# MCU042A_Antenna_RF.net
KiCad netlist of a schematic drawn in Altium Designer
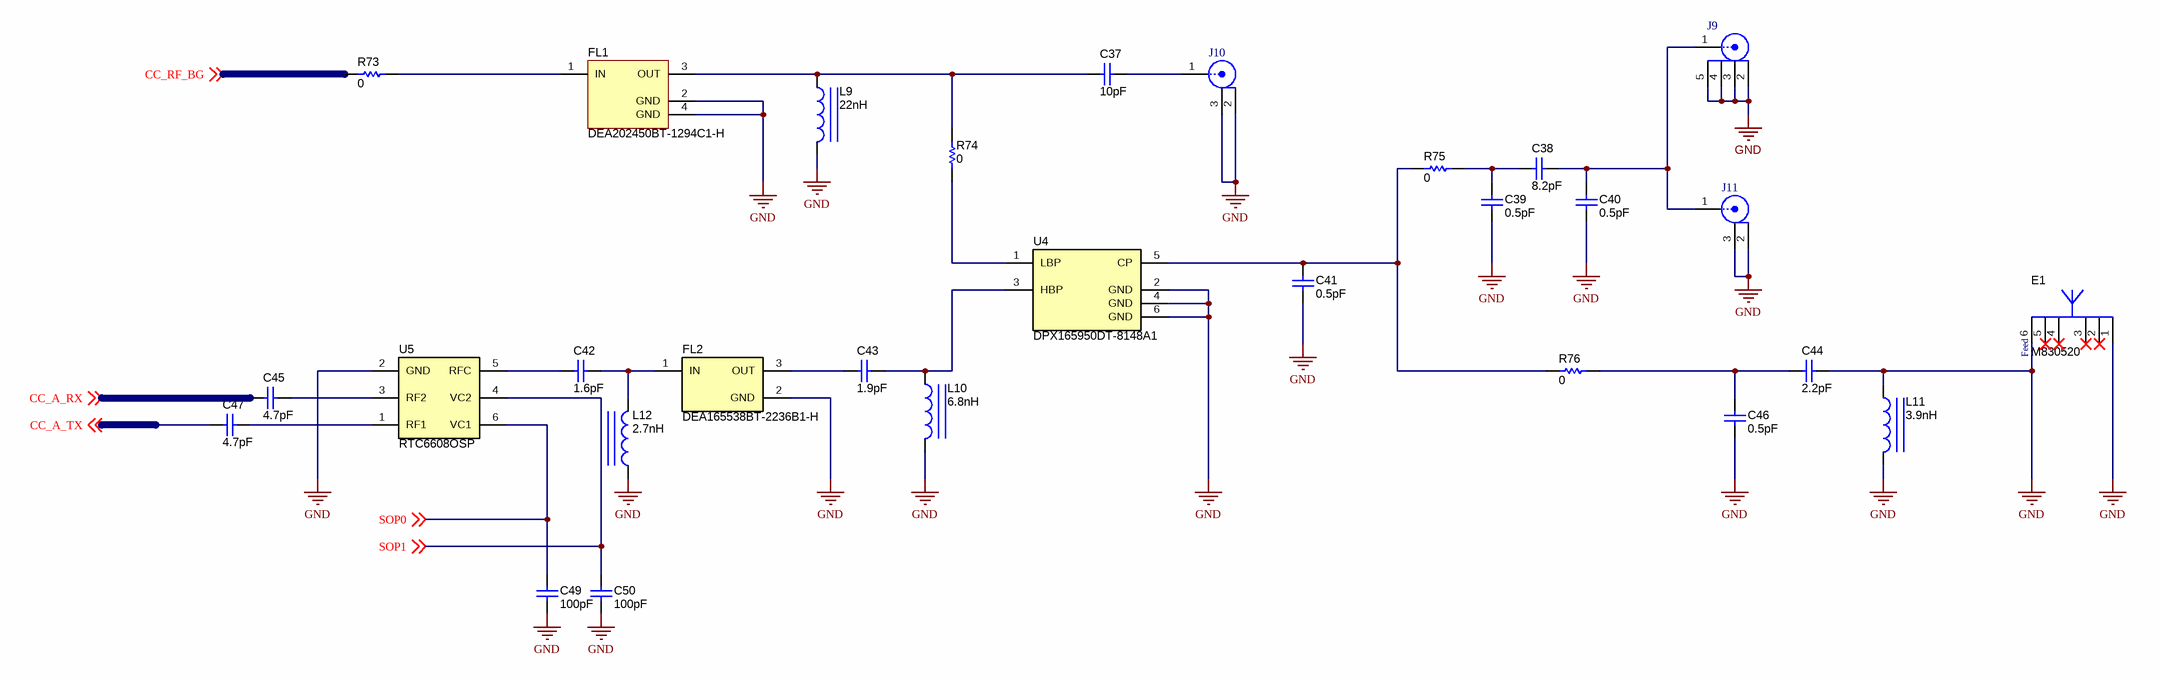
[diagram p0: MCU042A_Antenna_RF .SchDoc]

(export (version "E")
  (design (tool "Eeschema 10.0.6"))
  (components
    (comp (ref "C37")
      (value "CMP-0006408-2")
      (footprint "0402S")
      (description "CAP, CERM, 10 pF, 50 V, +/- 5%, C0G/NP0, 0402")
      (fields
        (field (name "PARTNUMBER") "GRM1555C1H100JA01D")
        (field (name "VALUEDISPLAYED") "10pF")
        (field (name "MANUFACTURER") "MuRata")
        (field (name "PUBLISHER") "Texas Instruments")
      )
      (libsource (lib "Altium Vault - TI") (part "CMP-0006408-2"))
    )
    (comp (ref "C38")
      (value "0402N8R2C500CT")
      (footprint "0402S")
      (description "CAP, CERM, 8.2 pF, 50 V,+/- 3%, C0G/NP0, 0402")
      (fields
        (field (name "PARTNUMBER") "GJM1555C1H8R2BB01D")
        (field (name "VALUEDISPLAYED") "8.2pF")
        (field (name "MANUFACTURER") "MuRata")
      )
      (libsource (lib "Altium Vault - TI") (part "Capacitor"))
    )
    (comp (ref "C39")
      (value "GJM1555C1HR50BB01J")
      (footprint "0402S")
      (description "CAP, CERM, 0.5 pF, 50 V,+/- 20%, C0G/NP0, 0402")
      (fields (field (name "VALUEDISPLAYED") "0.5pF") (field (name "MANUFACTURER") "MuRata"))
      (libsource (lib "Altium Vault - TI") (part "Capacitor"))
    )
    (comp (ref "C40")
      (value "GJM1555C1HR50BB01J")
      (footprint "0402S")
      (description "CAP, CERM, 0.5 pF, 50 V,+/- 20%, C0G/NP0, 0402")
      (fields (field (name "VALUEDISPLAYED") "0.5pF") (field (name "MANUFACTURER") "MuRata"))
      (libsource (lib "Altium Vault - TI") (part "Capacitor"))
    )
    (comp (ref "C41")
      (value "GJM1555C1HR50BB01J")
      (footprint "0402S")
      (description "CAP, CERM, 0.5 pF, 50 V,+/- 20%, C0G/NP0, 0402")
      (fields (field (name "VALUEDISPLAYED") "0.5pF") (field (name "MANUFACTURER") "MuRata"))
      (libsource (lib "Altium Vault - TI") (part "Capacitor"))
    )
    (comp (ref "C42")
      (value "GRM0335C1H1R6BA01D")
      (footprint "0201_033")
      (description "CAP, CERM, 1.6 pF, 50 V,+/- 7%, C0G/NP0, 0201")
      (fields (field (name "VALUEDISPLAYED") "1.6pF") (field (name "MANUFACTURER") "MuRata"))
      (libsource (lib "Altium Vault - TI") (part "Capacitor"))
    )
    (comp (ref "C43")
      (value "GJM1555C1H1R9WB01D")
      (footprint "0402S")
      (description "CAP, CERM, 1.9 pF, 50 V,+/- 2.6%, C0G/NP0, 0402")
      (fields
        (field (name "VALUEDISPLAYED") "1.9pF")
        (field (name "MANUFACTURER") "MuRata")
        (field (name "ALTERNATE PARTNUMBER") "GRM1555C1H1R9WA01D")
      )
      (libsource (lib "Altium Vault - TI") (part "Capacitor"))
    )
    (comp (ref "C44")
      (value "GJM1555C1H2R2BB01D")
      (footprint "0402S")
      (description "CAP, CERM, 2.2 pF, 50 V,+/- 4.5%, C0G/NP0, 0402")
      (fields
        (field (name "VALUEDISPLAYED") "2.2pF")
        (field (name "MANUFACTURER") "MuRata")
        (field (name "ALTERNATE PARTNUMBER") "GRM1555C1H2R2BA01D")
      )
      (libsource (lib "Altium Vault - TI") (part "Capacitor"))
    )
    (comp (ref "C45")
      (value "GRM0335C1H4R7BA01D")
      (footprint "0201_033")
      (description "CAP, CERM, 4.7 pF, 50 V,+/- 3%, C0G/NP0, 0201")
      (fields (field (name "VALUEDISPLAYED") "4.7pF") (field (name "MANUFACTURER") "MuRata"))
      (libsource (lib "Altium Vault - TI") (part "Capacitor"))
    )
    (comp (ref "C46")
      (value "GJM1555C1HR50BB01J")
      (footprint "0402S")
      (description "CAP, CERM, 0.5 pF, 50 V, +/- 10%, C0G/NP0, 0402")
      (fields
        (field (name "VALUEDISPLAYED") "0.5pF")
        (field (name "MANUFACTURER") "MuRata")
        (field (name "ALTERNATE PARTNUMBER") "----")
        (field (name "PUBLISHER") "Texas Instruments")
      )
      (libsource (lib "altium-import") (part "root_1_GRM1555C1H1R0BA01D_"))
    )
    (comp (ref "C47")
      (value "GRM0335C1H4R7BA01D")
      (footprint "0201_033")
      (description "CAP, CERM, 4.7 pF, 50 V,+/- 3%, C0G/NP0, 0201")
      (fields (field (name "VALUEDISPLAYED") "4.7pF") (field (name "MANUFACTURER") "MuRata"))
      (libsource (lib "Altium Vault - TI") (part "Capacitor"))
    )
    (comp (ref "C49")
      (value "CC0201JRNPO8BN101")
      (footprint "0201")
      (description "CAP, CERM, 100 pF, 25 V,+/- 5%, C0G/NP0, 0201")
      (fields
        (field (name "VALUEDISPLAYED") "100pF")
        (field (name "MANUFACTURER") "Yageo")
        (field (name "ALTERNATE PARTNUMBER") "C0603C0G1E101J030BA")
      )
      (libsource (lib "Altium Vault - TI") (part "Capacitor"))
    )
    (comp (ref "C50")
      (value "CC0201JRNPO8BN101")
      (footprint "0201")
      (description "CAP, CERM, 100 pF, 25 V,+/- 5%, C0G/NP0, 0201")
      (fields
        (field (name "VALUEDISPLAYED") "100pF")
        (field (name "MANUFACTURER") "Yageo")
        (field (name "ALTERNATE PARTNUMBER") "C0603C0G1E101J030BA")
      )
      (libsource (lib "Altium Vault - TI") (part "Capacitor"))
    )
    (comp (ref "E1")
      (value "M830520")
      (footprint "Ethertronics_M830520")
      (description "WLAN ANTENNA 802.11, SMD")
      (fields
        (field (name "MANUFACTURER") "Ethertronics")
        (field (name "ALTERNATE PARTNUMBER") "----")
        (field (name "PUBLISHER") "Texas Instruments")
      )
      (libsource (lib "Altium Vault - TI") (part "CMP-0001857-1"))
    )
    (comp (ref "FL1")
      (value "CMP-0002039-2")
      (footprint "TDK_DEA202450BT-1294C1-H")
      (description "Multilayer Chip Band Pass Filter For 2.4GHz W-LAN/Bluetooth, SMD")
      (fields
        (field (name "PARTNUMBER") "DEA202450BT-1294C1-H")
        (field (name "MANUFACTURER") "TDK")
        (field (name "ALTERNATE PARTNUMBER") "----")
        (field (name "PUBLISHER") "Texas Instruments")
      )
      (libsource (lib "Altium Vault - TI") (part "CMP-0002039-2"))
    )
    (comp (ref "FL2")
      (value "CMP-0002038-2")
      (footprint "TDK_DEA165538BT-2236B1-H")
      (description "Multilayer Band Pass Filter For 5GHz W-LAN/LTE-U")
      (fields
        (field (name "PARTNUMBER") "DEA165538BT-2236B1-H")
        (field (name "MANUFACTURER") "TDK")
        (field (name "ALTERNATE PARTNUMBER") "----")
        (field (name "PUBLISHER") "Texas Instruments")
      )
      (libsource (lib "Altium Vault - TI") (part "CMP-0002038-2"))
    )
    (comp (ref "J9")
      (value "CMP-0055832-1")
      (footprint "Hustsan_SMA-10V21-TGG")
      (description "Connector, SMA, Vertical, Gold, SMT")
      (fields
        (field (name "PARTNUMBER") "SMA-10V21-TGG")
        (field (name "MANUFACTURER") "Hus-Tsan Group Co., Ltd.")
        (field (name "PUBLISHER") "Texas Instruments")
      )
      (libsource (lib "Altium Vault - TI") (part "CMP-0055832-1"))
    )
    (comp (ref "J10")
      (value "U.FL-R-SMT-1(01)")
      (footprint "CONN_UFL-R-SMT-1")
      (description "Receptacle, Ultra Miniature Coaxial, Male Pin, 50 ohm, SMT")
      (fields
        (field (name "MANUFACTURER") "Hirose Electric Co. Ltd.")
        (field (name "ALTERNATE PARTNUMBER") "----")
        (field (name "PUBLISHER") "Texas Instruments")
      )
      (libsource (lib "Altium Vault - TI") (part "CMP-0075320-1"))
    )
    (comp (ref "J11")
      (value "U.FL-R-SMT-1(01)")
      (footprint "CONN_UFL-R-SMT-1")
      (description "Receptacle, Ultra Miniature Coaxial, Male Pin, 50 ohm, SMT")
      (fields
        (field (name "MANUFACTURER") "Hirose Electric Co. Ltd.")
        (field (name "ALTERNATE PARTNUMBER") "----")
        (field (name "PUBLISHER") "Texas Instruments")
      )
      (libsource (lib "Altium Vault - TI") (part "CMP-0075320-1"))
    )
    (comp (ref "L9")
      (value "LQG15HZ22NH02D")
      (footprint "0402S")
      (description "Inductor, Multilayer, Air Core, 22 nH, 0.35 A, 0.42 ohm, AEC-Q200 Grade 1, SMD")
      (fields (field (name "MANUFACTURER") "MuRata") (field (name "VALUEDISPLAYED") "22nH"))
      (libsource (lib "Altium Vault - TI") (part "Inductor_Iron"))
    )
    (comp (ref "L10")
      (value "LQG15HZ6N8H02D")
      (footprint "0402S")
      (description "Inductor, Multilayer, Air Core, 6.8 nH, 0.6 A, 0.22 ohm, AEC-Q200 Grade 1, SMD")
      (fields (field (name "MANUFACTURER") "MuRata") (field (name "VALUEDISPLAYED") "6.8nH"))
      (libsource (lib "Altium Vault - TI") (part "Inductor_Iron"))
    )
    (comp (ref "L11")
      (value "CMP-0058633-1")
      (footprint "IND_LQG15H")
      (description "Inductor, Multilayer, Air Core, 3.9 nH, 0.3 A, 0.18 ohm, SMD")
      (fields
        (field (name "PARTNUMBER") "LQG15HS3N9S02D")
        (field (name "VALUEDISPLAYED") "3.9nH")
        (field (name "MANUFACTURER") "MuRata")
        (field (name "PUBLISHER") "Texas Instruments")
      )
      (libsource (lib "Altium Vault - TI") (part "CMP-0058633-1"))
    )
    (comp (ref "L12")
      (value "LQG15WH2N7C02D")
      (footprint "0402S")
      (description "Inductor, Multilayer, Air Core, 2.7 nH, 0.9 A, 0.07 ohm, AEC-Q200 Grade 1, SMD")
      (fields (field (name "MANUFACTURER") "MuRata") (field (name "VALUEDISPLAYED") "2.7nH"))
      (libsource (lib "Altium Vault - TI") (part "Inductor_Iron"))
    )
    (comp (ref "R73")
      (value "CRCW02010000Z0ED")
      (footprint "0201")
      (description "RES, 0, 5%, 0.05 W, 0201")
      (fields
        (field (name "VALUEDISPLAYED") "0")
        (field (name "MANUFACTURER") "Vishay-Dale")
        (field (name "ALTERNATE PARTNUMBER") "ERJ-1GE0R00C")
      )
      (libsource (lib "Altium Vault - TI") (part "Resistor"))
    )
    (comp (ref "R74")
      (value "CMP-0026992-2")
      (footprint "0402S")
      (description "RES, 0, 5%, 0.063 W, 0402")
      (fields
        (field (name "PARTNUMBER") "ERJ-2GE0R00X")
        (field (name "VALUEDISPLAYED") "0")
        (field (name "MANUFACTURER") "Panasonic")
        (field (name "PUBLISHER") "Texas Instruments")
      )
      (libsource (lib "Altium Vault - TI") (part "CMP-0026992-2"))
    )
    (comp (ref "R75")
      (value "CMP-0026992-2")
      (footprint "0402S")
      (description "RES, 0, 5%, 0.063 W, 0402")
      (fields
        (field (name "PARTNUMBER") "ERJ-2GE0R00X")
        (field (name "VALUEDISPLAYED") "0")
        (field (name "MANUFACTURER") "Panasonic")
        (field (name "PUBLISHER") "Texas Instruments")
      )
      (libsource (lib "Altium Vault - TI") (part "CMP-0026992-2"))
    )
    (comp (ref "R76")
      (value "CMP-0026992-2")
      (footprint "0402S")
      (description "RES, 0, 5%, 0.063 W, 0402")
      (fields
        (field (name "PARTNUMBER") "ERJ-2GE0R00X")
        (field (name "VALUEDISPLAYED") "0")
        (field (name "MANUFACTURER") "Panasonic")
        (field (name "PUBLISHER") "Texas Instruments")
      )
      (libsource (lib "Altium Vault - TI") (part "CMP-0026992-2"))
    )
    (comp (ref "U4")
      (value "CMP-0002040-1")
      (footprint "TDK_DPX165950DT-8148A1")
      (description "Multilayer Diplexer for 2.4GHz W-LAN & Bluetooth / 5GHz W-LAN")
      (fields
        (field (name "PARTNUMBER") "DPX165950DT-8148A1")
        (field (name "MANUFACTURER") "TDK")
        (field (name "ALTERNATE PARTNUMBER") "----")
        (field (name "PUBLISHER") "Texas Instruments")
      )
      (libsource (lib "Altium Vault - TI") (part "CMP-0002040-1"))
    )
    (comp (ref "U5")
      (value "RTC6608OSP")
      (footprint "Richwave_RTC6608OSP")
      (description "0.03 GHz-6 GHz SPDT Switch")
      (fields
        (field (name "MANUFACTURER") "Richwave")
        (field (name "ALTERNATE PARTNUMBER") "Direct from MFR")
        (field (name "PUBLISHER") "Texas Instruments")
      )
      (libsource (lib "Altium Vault - TI") (part "CMP-0065464-1"))
    )
  )
  (nets
    (net (code "1") (name "CC_A_RX") (class "Default")
      (node (ref "C45") (pin "2") (pinfunction "2_2") (pintype "passive"))
    )
    (net (code "2") (name "CC_A_TX") (class "Default")
      (node (ref "C47") (pin "2") (pinfunction "2_2") (pintype "passive"))
    )
    (net (code "3") (name "CC_RF_BG") (class "Default")
      (node (ref "R73") (pin "2") (pinfunction "2_2") (pintype "passive"))
    )
    (net (code "4") (name "GND") (class "Default")
      (node (ref "C39") (pin "2") (pinfunction "2_2") (pintype "passive"))
      (node (ref "C40") (pin "2") (pinfunction "2_2") (pintype "passive"))
      (node (ref "C41") (pin "2") (pinfunction "2_2") (pintype "passive"))
      (node (ref "C44") (pin "2") (pinfunction "2_2") (pintype "passive"))
      (node (ref "C46") (pin "2") (pinfunction "2_2") (pintype "passive"))
      (node (ref "C49") (pin "2") (pinfunction "2_2") (pintype "passive"))
      (node (ref "C50") (pin "2") (pinfunction "2_2") (pintype "passive"))
      (node (ref "E1") (pin "1") (pinfunction "Feed_1") (pintype "passive"))
      (node (ref "E1") (pin "6") (pinfunction "6_6") (pintype "passive"))
      (node (ref "FL1") (pin "2") (pinfunction "GND_2") (pintype "power_in"))
      (node (ref "FL1") (pin "4") (pinfunction "GND_4") (pintype "power_in"))
      (node (ref "FL2") (pin "2") (pinfunction "GND_2") (pintype "power_in"))
      (node (ref "J10") (pin "2") (pinfunction "2_2") (pintype "passive"))
      (node (ref "J10") (pin "3") (pinfunction "3_3") (pintype "passive"))
      (node (ref "J11") (pin "2") (pinfunction "2_2") (pintype "passive"))
      (node (ref "J11") (pin "3") (pinfunction "3_3") (pintype "passive"))
      (node (ref "J9") (pin "2") (pinfunction "2_2") (pintype "passive"))
      (node (ref "J9") (pin "3") (pinfunction "3_3") (pintype "passive"))
      (node (ref "J9") (pin "4") (pinfunction "4_4") (pintype "passive"))
      (node (ref "J9") (pin "5") (pinfunction "5_5") (pintype "passive"))
      (node (ref "L10") (pin "2") (pinfunction "2_2") (pintype "passive"))
      (node (ref "L11") (pin "1") (pinfunction "1_1") (pintype "passive"))
      (node (ref "L11") (pin "2") (pinfunction "2_2") (pintype "passive"))
      (node (ref "L12") (pin "1") (pinfunction "1_1") (pintype "passive"))
      (node (ref "L9") (pin "2") (pinfunction "2_2") (pintype "passive"))
      (node (ref "U4") (pin "2") (pinfunction "GND_2") (pintype "power_in"))
      (node (ref "U4") (pin "4") (pinfunction "GND_4") (pintype "power_in"))
      (node (ref "U4") (pin "6") (pinfunction "GND_6") (pintype "power_in"))
      (node (ref "U5") (pin "2") (pinfunction "GND_2") (pintype "power_in"))
    )
    (net (code "5") (name "Net-(C37-Pad2)") (class "Default")
      (node (ref "C37") (pin "2") (pinfunction "2_2") (pintype "passive"))
      (node (ref "J10") (pin "1") (pinfunction "1_1") (pintype "passive"))
    )
    (net (code "6") (name "Net-(C38-Pad1)") (class "Default")
      (node (ref "C38") (pin "1") (pinfunction "1_1") (pintype "passive"))
      (node (ref "C39") (pin "1") (pinfunction "1_1") (pintype "passive"))
      (node (ref "R75") (pin "2") (pinfunction "2_2") (pintype "passive"))
    )
    (net (code "7") (name "Net-(C38-Pad2)") (class "Default")
      (node (ref "C38") (pin "2") (pinfunction "2_2") (pintype "passive"))
      (node (ref "C40") (pin "1") (pinfunction "1_1") (pintype "passive"))
      (node (ref "J11") (pin "1") (pinfunction "1_1") (pintype "passive"))
      (node (ref "J9") (pin "1") (pinfunction "1_1") (pintype "passive"))
    )
    (net (code "8") (name "Net-(C44-Pad1)") (class "Default")
      (node (ref "C44") (pin "1") (pinfunction "1_1") (pintype "passive"))
      (node (ref "C46") (pin "1") (pinfunction "1_1") (pintype "passive"))
      (node (ref "R76") (pin "2") (pinfunction "2_2") (pintype "passive"))
    )
    (net (code "9") (name "Net-(FL1-IN)") (class "Default")
      (node (ref "FL1") (pin "1") (pinfunction "IN_1") (pintype "passive"))
      (node (ref "R73") (pin "1") (pinfunction "1_1") (pintype "passive"))
    )
    (net (code "10") (name "Net-(FL1-OUT)") (class "Default")
      (node (ref "C37") (pin "1") (pinfunction "1_1") (pintype "passive"))
      (node (ref "FL1") (pin "3") (pinfunction "OUT_3") (pintype "passive"))
      (node (ref "L9") (pin "1") (pinfunction "1_1") (pintype "passive"))
      (node (ref "R74") (pin "2") (pinfunction "2_2") (pintype "passive"))
    )
    (net (code "11") (name "Net-(FL2-IN)") (class "Default")
      (node (ref "C42") (pin "1") (pinfunction "1_1") (pintype "passive"))
      (node (ref "FL2") (pin "1") (pinfunction "IN_1") (pintype "passive"))
      (node (ref "L12") (pin "2") (pinfunction "2_2") (pintype "passive"))
    )
    (net (code "12") (name "Net-(FL2-OUT)") (class "Default")
      (node (ref "C43") (pin "1") (pinfunction "1_1") (pintype "passive"))
      (node (ref "FL2") (pin "3") (pinfunction "OUT_3") (pintype "passive"))
    )
    (net (code "13") (name "Net-(U4-CP)") (class "Default")
      (node (ref "C41") (pin "1") (pinfunction "1_1") (pintype "passive"))
      (node (ref "R75") (pin "1") (pinfunction "1_1") (pintype "passive"))
      (node (ref "R76") (pin "1") (pinfunction "1_1") (pintype "passive"))
      (node (ref "U4") (pin "5") (pinfunction "CP_5") (pintype "passive"))
    )
    (net (code "14") (name "Net-(U4-HBP)") (class "Default")
      (node (ref "C43") (pin "2") (pinfunction "2_2") (pintype "passive"))
      (node (ref "L10") (pin "1") (pinfunction "1_1") (pintype "passive"))
      (node (ref "U4") (pin "3") (pinfunction "HBP_3") (pintype "passive"))
    )
    (net (code "15") (name "Net-(U4-LBP)") (class "Default")
      (node (ref "R74") (pin "1") (pinfunction "1_1") (pintype "passive"))
      (node (ref "U4") (pin "1") (pinfunction "LBP_1") (pintype "passive"))
    )
    (net (code "16") (name "Net-(U5-RF1)") (class "Default")
      (node (ref "C47") (pin "1") (pinfunction "1_1") (pintype "passive"))
      (node (ref "U5") (pin "1") (pinfunction "RF1_1") (pintype "passive"))
    )
    (net (code "17") (name "Net-(U5-RF2)") (class "Default")
      (node (ref "C45") (pin "1") (pinfunction "1_1") (pintype "passive"))
      (node (ref "U5") (pin "3") (pinfunction "RF2_3") (pintype "passive"))
    )
    (net (code "18") (name "Net-(U5-RFC)") (class "Default")
      (node (ref "C42") (pin "2") (pinfunction "2_2") (pintype "passive"))
      (node (ref "U5") (pin "5") (pinfunction "RFC_5") (pintype "passive"))
    )
    (net (code "19") (name "SOP0") (class "Default")
      (node (ref "C49") (pin "1") (pinfunction "1_1") (pintype "passive"))
      (node (ref "U5") (pin "6") (pinfunction "VC1_6") (pintype "power_in"))
    )
    (net (code "20") (name "SOP1") (class "Default")
      (node (ref "C50") (pin "1") (pinfunction "1_1") (pintype "passive"))
      (node (ref "U5") (pin "4") (pinfunction "VC2_4") (pintype "power_in"))
    )
    (net (code "21") (name "unconnected-(E1-Feed-Pad4)") (class "Default")
      (node (ref "E1") (pin "4") (pinfunction "Feed_4") (pintype "passive+no_connect"))
    )
    (net (code "22") (name "unconnected-(E1-GND-Pad2)") (class "Default")
      (node (ref "E1") (pin "2") (pinfunction "GND_2") (pintype "power_in+no_connect"))
    )
    (net (code "23") (name "unconnected-(E1-GND-Pad3)") (class "Default")
      (node (ref "E1") (pin "3") (pinfunction "GND_3") (pintype "power_in+no_connect"))
    )
    (net (code "24") (name "unconnected-(E1-Pad5)") (class "Default")
      (node (ref "E1") (pin "5") (pinfunction "5_5") (pintype "passive+no_connect"))
    )
  )
)
